# peripherals.net
KiCad netlist of a schematic drawn in Altium Designer
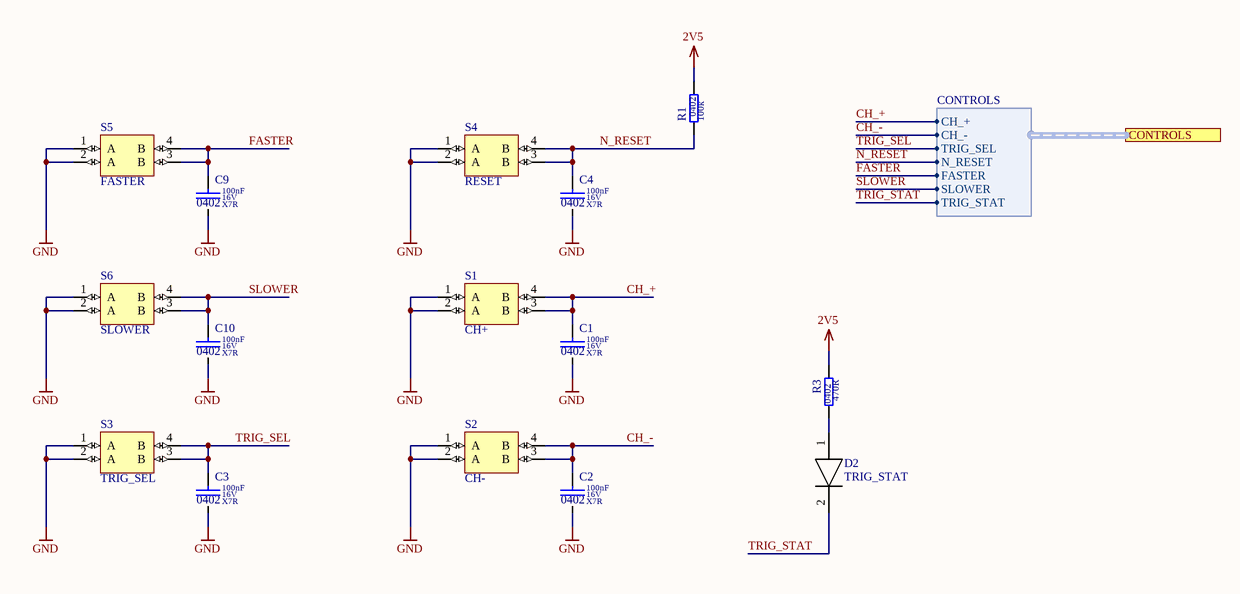
[diagram p0: peripherals.SchDoc]

(export (version "E")
  (design (tool "Eeschema 10.0.6"))
  (components
    (comp (ref "C1")
      (value "100nF")
      (footprint "C_0402_1005")
      (description "Capacitor")
      (fields
        (field (name "DIELECTRIC") "X7R")
        (field (name "VOLTAGE") "16V")
        (field (name "SCH_FOOTPRINT") "0402")
        (field (name "PART NUMBER") "C_100nF_16V_X7R_0402_10")
        (field (name "MANUFACTURER") "Murata")
      )
      (libsource (lib "Library") (part "C"))
    )
    (comp (ref "C2")
      (value "100nF")
      (footprint "C_0402_1005")
      (description "Capacitor")
      (fields
        (field (name "DIELECTRIC") "X7R")
        (field (name "VOLTAGE") "16V")
        (field (name "SCH_FOOTPRINT") "0402")
        (field (name "PART NUMBER") "C_100nF_16V_X7R_0402_10")
        (field (name "MANUFACTURER") "Murata")
      )
      (libsource (lib "Library") (part "C"))
    )
    (comp (ref "C3")
      (value "100nF")
      (footprint "C_0402_1005")
      (description "Capacitor")
      (fields
        (field (name "DIELECTRIC") "X7R")
        (field (name "VOLTAGE") "16V")
        (field (name "SCH_FOOTPRINT") "0402")
        (field (name "PART NUMBER") "C_100nF_16V_X7R_0402_10")
        (field (name "MANUFACTURER") "Murata")
      )
      (libsource (lib "Library") (part "C"))
    )
    (comp (ref "C4")
      (value "100nF")
      (footprint "C_0402_1005")
      (description "Capacitor")
      (fields
        (field (name "DIELECTRIC") "X7R")
        (field (name "VOLTAGE") "16V")
        (field (name "SCH_FOOTPRINT") "0402")
        (field (name "PART NUMBER") "C_100nF_16V_X7R_0402_10")
        (field (name "MANUFACTURER") "Murata")
      )
      (libsource (lib "Library") (part "C"))
    )
    (comp (ref "C9")
      (value "100nF")
      (footprint "C_0402_1005")
      (description "Capacitor")
      (fields
        (field (name "DIELECTRIC") "X7R")
        (field (name "VOLTAGE") "16V")
        (field (name "SCH_FOOTPRINT") "0402")
        (field (name "PART NUMBER") "C_100nF_16V_X7R_0402_10")
        (field (name "MANUFACTURER") "Murata")
      )
      (libsource (lib "Library") (part "C"))
    )
    (comp (ref "C10")
      (value "100nF")
      (footprint "C_0402_1005")
      (description "Capacitor")
      (fields
        (field (name "DIELECTRIC") "X7R")
        (field (name "VOLTAGE") "16V")
        (field (name "SCH_FOOTPRINT") "0402")
        (field (name "PART NUMBER") "C_100nF_16V_X7R_0402_10")
        (field (name "MANUFACTURER") "Murata")
      )
      (libsource (lib "Library") (part "C"))
    )
    (comp (ref "D2")
      (value "TRIG_STAT")
      (footprint "LED_5mm")
      (description "LED_5mm Diameter")
      (libsource (lib "soldering_station") (part "LED_5mm"))
    )
    (comp (ref "R1")
      (value "100k")
      (footprint "R_0402_1005")
      (fields
        (field (name "SCH_FOOTPRINT") "0402")
        (field (name "PART NUMBER") "R_100k_0402_1")
        (field (name "VOLTAGE") "50V")
        (field (name "POWER") "63mW")
      )
      (libsource (lib "Library") (part "R"))
    )
    (comp (ref "R3")
      (value "470R")
      (footprint "R_0402_1005")
      (fields
        (field (name "SCH_FOOTPRINT") "0402")
        (field (name "PART NUMBER") "R_470R_0402_1")
        (field (name "VOLTAGE") "50V")
        (field (name "POWER") "63mW")
      )
      (libsource (lib "Library") (part "R"))
    )
    (comp (ref "S1")
      (value "CH+")
      (footprint "TACT-613N-F")
      (libsource (lib "soldering_station") (part "TACT-613N-F"))
    )
    (comp (ref "S2")
      (value "CH-")
      (footprint "TACT-613N-F")
      (libsource (lib "soldering_station") (part "TACT-613N-F"))
    )
    (comp (ref "S3")
      (value "TRIG_SEL")
      (footprint "TACT-613N-F")
      (libsource (lib "soldering_station") (part "TACT-613N-F"))
    )
    (comp (ref "S4")
      (value "RESET")
      (footprint "TACT-613N-F")
      (libsource (lib "soldering_station") (part "TACT-613N-F"))
    )
    (comp (ref "S5")
      (value "FASTER")
      (footprint "TACT-613N-F")
      (libsource (lib "soldering_station") (part "TACT-613N-F"))
    )
    (comp (ref "S6")
      (value "SLOWER")
      (footprint "TACT-613N-F")
      (libsource (lib "soldering_station") (part "TACT-613N-F"))
    )
  )
  (nets
    (net (code "2") (name "/CH_+") (class "Default")
      (node (ref "C1") (pin "1") (pinfunction "1_1") (pintype "passive"))
      (node (ref "S1") (pin "3") (pinfunction "B_3") (pintype "bidirectional"))
      (node (ref "S1") (pin "4") (pinfunction "B_4") (pintype "bidirectional"))
    )
    (net (code "3") (name "/CH_-") (class "Default")
      (node (ref "C2") (pin "1") (pinfunction "1_1") (pintype "passive"))
      (node (ref "S2") (pin "3") (pinfunction "B_3") (pintype "bidirectional"))
      (node (ref "S2") (pin "4") (pinfunction "B_4") (pintype "bidirectional"))
    )
    (net (code "4") (name "/FASTER") (class "Default")
      (node (ref "C9") (pin "1") (pinfunction "1_1") (pintype "passive"))
      (node (ref "S5") (pin "3") (pinfunction "B_3") (pintype "bidirectional"))
      (node (ref "S5") (pin "4") (pinfunction "B_4") (pintype "bidirectional"))
    )
    (net (code "5") (name "/N_RESET") (class "Default")
      (node (ref "C4") (pin "1") (pinfunction "1_1") (pintype "passive"))
      (node (ref "R1") (pin "1") (pinfunction "1_1") (pintype "passive"))
      (node (ref "S4") (pin "3") (pinfunction "B_3") (pintype "bidirectional"))
      (node (ref "S4") (pin "4") (pinfunction "B_4") (pintype "bidirectional"))
    )
    (net (code "6") (name "/SLOWER") (class "Default")
      (node (ref "C10") (pin "1") (pinfunction "1_1") (pintype "passive"))
      (node (ref "S6") (pin "3") (pinfunction "B_3") (pintype "bidirectional"))
      (node (ref "S6") (pin "4") (pinfunction "B_4") (pintype "bidirectional"))
    )
    (net (code "7") (name "/TRIG_SEL") (class "Default")
      (node (ref "C3") (pin "1") (pinfunction "1_1") (pintype "passive"))
      (node (ref "S3") (pin "3") (pinfunction "B_3") (pintype "bidirectional"))
      (node (ref "S3") (pin "4") (pinfunction "B_4") (pintype "bidirectional"))
    )
    (net (code "8") (name "/TRIG_STAT") (class "Default")
      (node (ref "D2") (pin "2") (pinfunction "Cathode_2") (pintype "passive"))
    )
    (net (code "10") (name "2V5") (class "Default")
      (node (ref "R1") (pin "2") (pinfunction "2_2") (pintype "passive"))
      (node (ref "R3") (pin "1") (pinfunction "1_1") (pintype "passive"))
    )
    (net (code "11") (name "GND") (class "Default")
      (node (ref "C1") (pin "2") (pinfunction "2_2") (pintype "passive"))
      (node (ref "C10") (pin "2") (pinfunction "2_2") (pintype "passive"))
      (node (ref "C2") (pin "2") (pinfunction "2_2") (pintype "passive"))
      (node (ref "C3") (pin "2") (pinfunction "2_2") (pintype "passive"))
      (node (ref "C4") (pin "2") (pinfunction "2_2") (pintype "passive"))
      (node (ref "C9") (pin "2") (pinfunction "2_2") (pintype "passive"))
      (node (ref "S1") (pin "1") (pinfunction "A_1") (pintype "bidirectional"))
      (node (ref "S1") (pin "2") (pinfunction "A_2") (pintype "bidirectional"))
      (node (ref "S2") (pin "1") (pinfunction "A_1") (pintype "bidirectional"))
      (node (ref "S2") (pin "2") (pinfunction "A_2") (pintype "bidirectional"))
      (node (ref "S3") (pin "1") (pinfunction "A_1") (pintype "bidirectional"))
      (node (ref "S3") (pin "2") (pinfunction "A_2") (pintype "bidirectional"))
      (node (ref "S4") (pin "1") (pinfunction "A_1") (pintype "bidirectional"))
      (node (ref "S4") (pin "2") (pinfunction "A_2") (pintype "bidirectional"))
      (node (ref "S5") (pin "1") (pinfunction "A_1") (pintype "bidirectional"))
      (node (ref "S5") (pin "2") (pinfunction "A_2") (pintype "bidirectional"))
      (node (ref "S6") (pin "1") (pinfunction "A_1") (pintype "bidirectional"))
      (node (ref "S6") (pin "2") (pinfunction "A_2") (pintype "bidirectional"))
    )
    (net (code "12") (name "Net-(D2-Anode)") (class "Default")
      (node (ref "D2") (pin "1") (pinfunction "Anode_1") (pintype "passive"))
      (node (ref "R3") (pin "2") (pinfunction "2_2") (pintype "passive"))
    )
  )
)
